# s02_power.net
KiCad netlist of a schematic drawn in Altium Designer
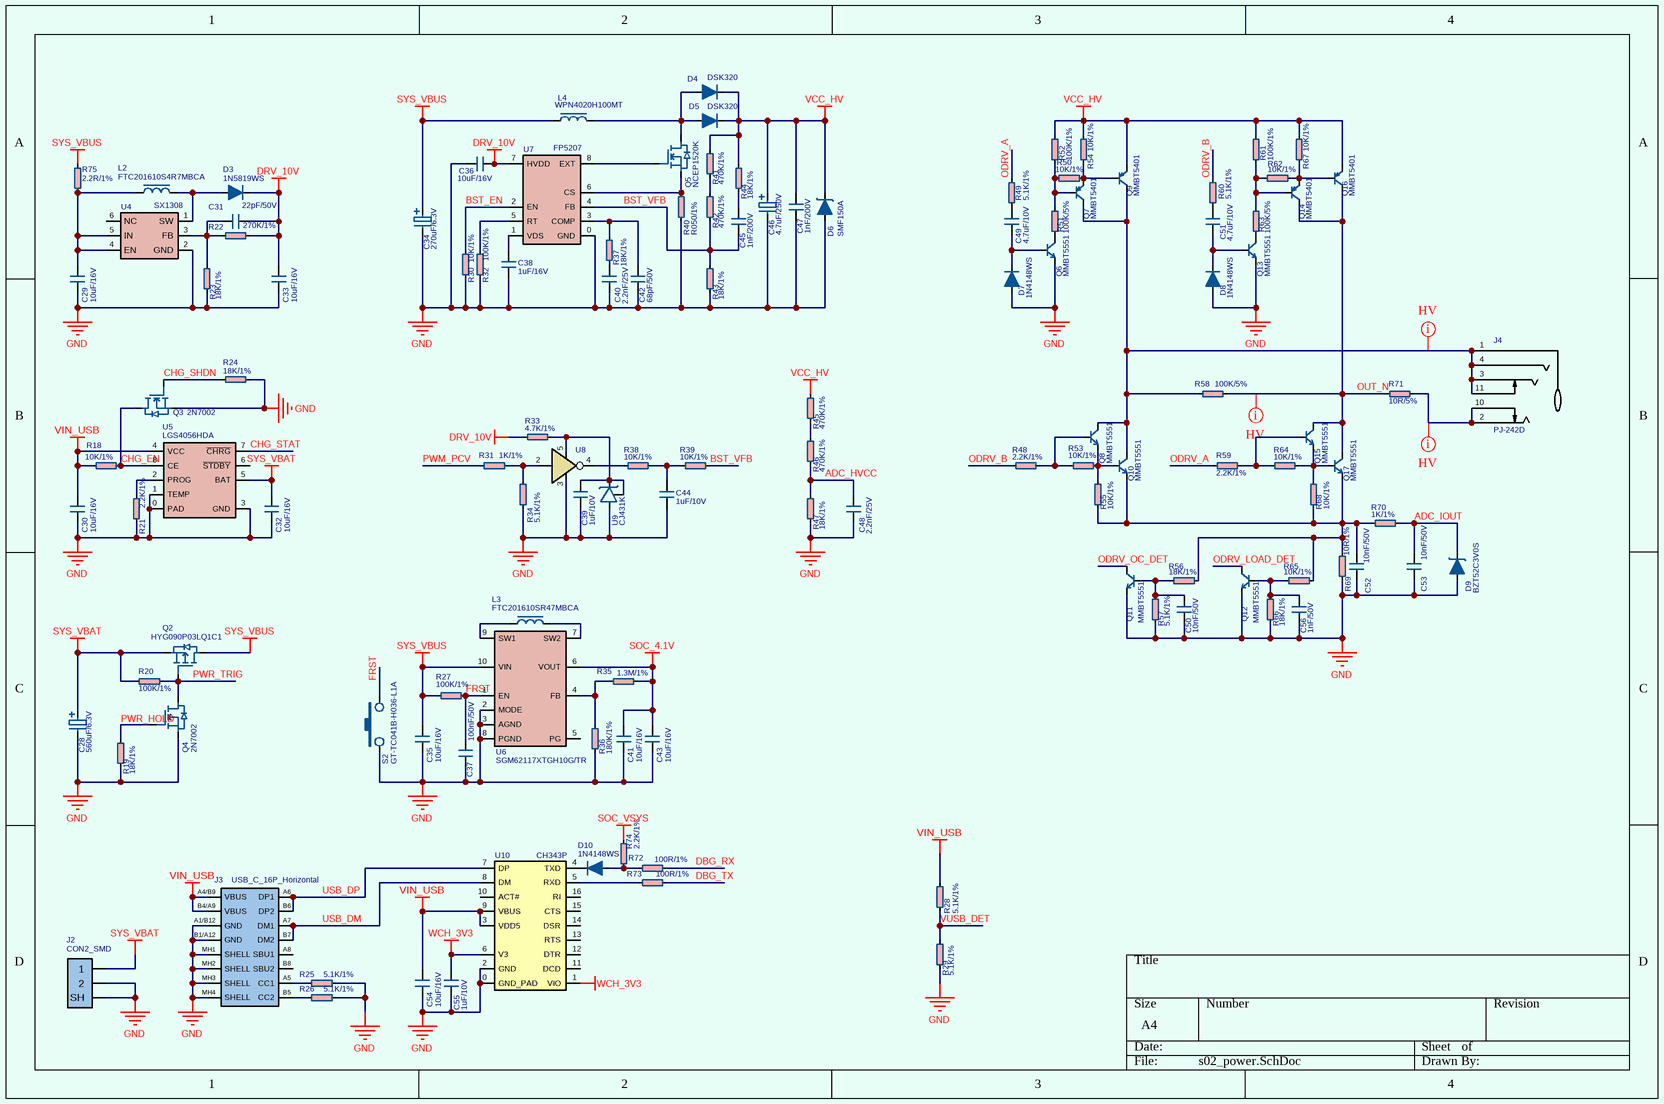
[diagram p0: s02_power.SchDoc]

(export (version "E")
  (design (tool "Eeschema 10.0.6"))
  (components
    (comp (ref "C28")
      (value "560uF/6.3V")
      (footprint "CAP_EL_DIP_6.3X11_HOR_REV")
      (libsource (lib "LibMySelf_SCHLIB") (part "CAP_EL"))
    )
    (comp (ref "C29")
      (value "10uF/16V")
      (footprint "0603C")
      (libsource (lib "LibMySelf_SCHLIB") (part "CAP"))
    )
    (comp (ref "C30")
      (value "10uF/16V")
      (footprint "0603C")
      (libsource (lib "LibMySelf_SCHLIB") (part "CAP"))
    )
    (comp (ref "C31")
      (value "22pF/50V")
      (footprint "0402C")
      (libsource (lib "LibMySelf_SCHLIB") (part "CAP"))
    )
    (comp (ref "C32")
      (value "10uF/16V")
      (footprint "0603C")
      (libsource (lib "LibMySelf_SCHLIB") (part "CAP"))
    )
    (comp (ref "C33")
      (value "10uF/16V")
      (footprint "0603C")
      (libsource (lib "LibMySelf_SCHLIB") (part "CAP"))
    )
    (comp (ref "C34")
      (value "270uF/6.3V")
      (footprint "CAP_EL_DIP_6.3X11_HOR_REV")
      (libsource (lib "LibMySelf_SCHLIB") (part "CAP_EL"))
    )
    (comp (ref "C35")
      (value "10uF/16V")
      (footprint "0603C")
      (libsource (lib "LibMySelf_SCHLIB") (part "CAP"))
    )
    (comp (ref "C36")
      (value "10uF/16V")
      (footprint "0603C")
      (libsource (lib "LibMySelf_SCHLIB") (part "CAP"))
    )
    (comp (ref "C37")
      (value "100nF/50V")
      (footprint "0402C")
      (libsource (lib "LibMySelf_SCHLIB") (part "CAP"))
    )
    (comp (ref "C38") (value "1uF/16V") (footprint "0402C") (libsource (lib "LibMySelf_SCHLIB") (part "CAP")))
    (comp (ref "C39") (value "1uF/10V") (footprint "0402C") (libsource (lib "LibMySelf_SCHLIB") (part "CAP")))
    (comp (ref "C40")
      (value "2.2nF/25V")
      (footprint "0402C")
      (libsource (lib "LibMySelf_SCHLIB") (part "CAP"))
    )
    (comp (ref "C41")
      (value "10uF/16V")
      (footprint "0603C")
      (libsource (lib "LibMySelf_SCHLIB") (part "CAP"))
    )
    (comp (ref "C42")
      (value "68pF/50V")
      (footprint "0402C")
      (libsource (lib "LibMySelf_SCHLIB") (part "CAP"))
    )
    (comp (ref "C43")
      (value "10uF/16V")
      (footprint "0603C")
      (libsource (lib "LibMySelf_SCHLIB") (part "CAP"))
    )
    (comp (ref "C44") (value "1uF/10V") (footprint "0402C") (libsource (lib "LibMySelf_SCHLIB") (part "CAP")))
    (comp (ref "C45")
      (value "1nF/200V")
      (footprint "0805C_N_HD")
      (description "CC0805JRNPOABN102")
      (libsource (lib "LibMySelf_SCHLIB") (part "CAP"))
    )
    (comp (ref "C46")
      (value "4.7uF/250V")
      (footprint "CAP_EL_DIP_6.3X11_HOR_REV")
      (libsource (lib "LibMySelf_SCHLIB") (part "CAP_EL"))
    )
    (comp (ref "C47")
      (value "1nF/200V")
      (footprint "0805C_N_HD")
      (description "CC0805JRNPOABN102")
      (libsource (lib "LibMySelf_SCHLIB") (part "CAP"))
    )
    (comp (ref "C48")
      (value "2.2nF/25V")
      (footprint "0402C")
      (libsource (lib "LibMySelf_SCHLIB") (part "CAP"))
    )
    (comp (ref "C49")
      (value "4.7uF/10V")
      (footprint "0402C")
      (libsource (lib "LibMySelf_SCHLIB") (part "CAP"))
    )
    (comp (ref "C50")
      (value "10nF/50V")
      (footprint "0402C")
      (libsource (lib "LibMySelf_SCHLIB") (part "CAP"))
    )
    (comp (ref "C51")
      (value "4.7uF/10V")
      (footprint "0402C")
      (libsource (lib "LibMySelf_SCHLIB") (part "CAP"))
    )
    (comp (ref "C52")
      (value "10nF/50V")
      (footprint "0402C")
      (libsource (lib "LibMySelf_SCHLIB") (part "CAP"))
    )
    (comp (ref "C53")
      (value "10nF/50V")
      (footprint "0402C")
      (libsource (lib "LibMySelf_SCHLIB") (part "CAP"))
    )
    (comp (ref "C54")
      (value "10uF/16V")
      (footprint "0603C")
      (libsource (lib "LibMySelf_SCHLIB") (part "CAP"))
    )
    (comp (ref "C55") (value "1uF/10V") (footprint "0402C") (libsource (lib "LibMySelf_SCHLIB") (part "CAP")))
    (comp (ref "C56") (value "1nF/50V") (footprint "0402C") (libsource (lib "LibMySelf_SCHLIB") (part "CAP")))
    (comp (ref "D3")
      (value "1N5819WS")
      (footprint "SOD323_N")
      (libsource (lib "LibMySelf_SCHLIB") (part "VD"))
    )
    (comp (ref "D4")
      (value "DSK320")
      (footprint "SOD123_N_HD")
      (libsource (lib "LibMySelf_SCHLIB") (part "VD"))
    )
    (comp (ref "D5")
      (value "DSK320")
      (footprint "SOD123_N_HD")
      (libsource (lib "LibMySelf_SCHLIB") (part "VD"))
    )
    (comp (ref "D6")
      (value "SMF150A")
      (footprint "SOD123_N_HD")
      (libsource (lib "LibMySelf_SCHLIB") (part "VS"))
    )
    (comp (ref "D7") (value "1N4148WS") (footprint "SOD323") (libsource (lib "LibMySelf_SCHLIB") (part "VD")))
    (comp (ref "D8") (value "1N4148WS") (footprint "SOD323") (libsource (lib "LibMySelf_SCHLIB") (part "VD")))
    (comp (ref "D9")
      (value "BZT52C3V0S")
      (footprint "SOD323_N")
      (libsource (lib "LibMySelf_SCHLIB") (part "VS"))
    )
    (comp (ref "D10")
      (value "1N4148WS")
      (footprint "SOD323")
      (libsource (lib "LibMySelf_SCHLIB") (part "VD"))
    )
    (comp (ref "J2")
      (value "CON2_SMD")
      (footprint "PRT_1.25MM_2PIN_HOR_SMD")
      (libsource (lib "LibMySelf_SCHLIB") (part "CON2_SMD"))
    )
    (comp (ref "J3")
      (value "USB_C_16P_Horizontal")
      (footprint "USB_C_16P_FEMALE_HOR_L7.3_HD")
      (libsource (lib "LibMySelf_SCHLIB") (part "USB_TYPEC_16P_Horizontal_4MP"))
    )
    (comp (ref "J4")
      (value "PJ-242D")
      (footprint "CON_AUDIO_PJ_242")
      (libsource (lib "LibMySelf_SCHLIB") (part "CON_AUDIO_PJ_242D"))
    )
    (comp (ref "L2")
      (value "FTC201610S4R7MBCA")
      (footprint "INDUCTOR_0806_HD")
      (libsource (lib "LibMySelf_SCHLIB") (part "INDUCTOR"))
    )
    (comp (ref "L3")
      (value "FTC201610SR47MBCA")
      (footprint "INDUCTOR_0806_HD")
      (libsource (lib "LibMySelf_SCHLIB") (part "INDUCTOR"))
    )
    (comp (ref "L4")
      (value "WPN4020H100MT")
      (footprint "INDUCTOR_SWPA4020S")
      (libsource (lib "LibMySelf_SCHLIB") (part "INDUCTOR"))
    )
    (comp (ref "Q2")
      (value "HYG090P03LQ1C1")
      (footprint "DFN8_MOS_3X3")
      (libsource (lib "LibMySelf_SCHLIB") (part "MOS_P"))
    )
    (comp (ref "Q3")
      (value "2N7002")
      (footprint "SOT23_MOS")
      (libsource (lib "LibMySelf_SCHLIB") (part "MOS_N"))
    )
    (comp (ref "Q4")
      (value "2N7002")
      (footprint "SOT23_MOS")
      (libsource (lib "LibMySelf_SCHLIB") (part "MOS_N"))
    )
    (comp (ref "Q5")
      (value "NCEP1520K")
      (footprint "TO252_MOS")
      (libsource (lib "LibMySelf_SCHLIB") (part "MOS_N"))
    )
    (comp (ref "Q6")
      (value "MMBT5551")
      (footprint "SOT23_BCE")
      (libsource (lib "LibMySelf_SCHLIB") (part "BJT_NPN"))
    )
    (comp (ref "Q7")
      (value "MMBT5401")
      (footprint "SOT23_BCE")
      (libsource (lib "LibMySelf_SCHLIB") (part "BJT_PNP"))
    )
    (comp (ref "Q8")
      (value "MMBT5551")
      (footprint "SOT23_BCE")
      (libsource (lib "LibMySelf_SCHLIB") (part "BJT_NPN"))
    )
    (comp (ref "Q9")
      (value "MMBT5401")
      (footprint "SOT23_BCE")
      (libsource (lib "LibMySelf_SCHLIB") (part "BJT_PNP"))
    )
    (comp (ref "Q10")
      (value "MMBT5551")
      (footprint "SOT23_BCE")
      (libsource (lib "LibMySelf_SCHLIB") (part "BJT_NPN"))
    )
    (comp (ref "Q11")
      (value "MMBT5551")
      (footprint "SOT23_BCE")
      (libsource (lib "LibMySelf_SCHLIB") (part "BJT_NPN"))
    )
    (comp (ref "Q12")
      (value "MMBT5551")
      (footprint "SOT23_BCE")
      (libsource (lib "LibMySelf_SCHLIB") (part "BJT_NPN"))
    )
    (comp (ref "Q13")
      (value "MMBT5551")
      (footprint "SOT23_BCE")
      (libsource (lib "LibMySelf_SCHLIB") (part "BJT_NPN"))
    )
    (comp (ref "Q14")
      (value "MMBT5401")
      (footprint "SOT23_BCE")
      (libsource (lib "LibMySelf_SCHLIB") (part "BJT_PNP"))
    )
    (comp (ref "Q15")
      (value "MMBT5551")
      (footprint "SOT23_BCE")
      (libsource (lib "LibMySelf_SCHLIB") (part "BJT_NPN"))
    )
    (comp (ref "Q16")
      (value "MMBT5401")
      (footprint "SOT23_BCE")
      (libsource (lib "LibMySelf_SCHLIB") (part "BJT_PNP"))
    )
    (comp (ref "Q17")
      (value "MMBT5551")
      (footprint "SOT23_BCE")
      (libsource (lib "LibMySelf_SCHLIB") (part "BJT_NPN"))
    )
    (comp (ref "R18") (value "10K/1%") (footprint "0402R") (libsource (lib "LibMySelf_SCHLIB") (part "RES")))
    (comp (ref "R19") (value "18K/1%") (footprint "0402R") (libsource (lib "LibMySelf_SCHLIB") (part "RES")))
    (comp (ref "R20") (value "100K/1%") (footprint "0402R") (libsource (lib "LibMySelf_SCHLIB") (part "RES")))
    (comp (ref "R21") (value "2.2K/1%") (footprint "0402R") (libsource (lib "LibMySelf_SCHLIB") (part "RES")))
    (comp (ref "R22") (value "270K/1%") (footprint "0402R") (libsource (lib "LibMySelf_SCHLIB") (part "RES")))
    (comp (ref "R23") (value "18K/1%") (footprint "0402R") (libsource (lib "LibMySelf_SCHLIB") (part "RES")))
    (comp (ref "R24") (value "18K/1%") (footprint "0402R") (libsource (lib "LibMySelf_SCHLIB") (part "RES")))
    (comp (ref "R25") (value "5.1K/1%") (footprint "0402R") (libsource (lib "LibMySelf_SCHLIB") (part "RES")))
    (comp (ref "R26") (value "5.1K/1%") (footprint "0402R") (libsource (lib "LibMySelf_SCHLIB") (part "RES")))
    (comp (ref "R27") (value "100K/1%") (footprint "0402R") (libsource (lib "LibMySelf_SCHLIB") (part "RES")))
    (comp (ref "R28") (value "5.1K/1%") (footprint "0402R") (libsource (lib "LibMySelf_SCHLIB") (part "RES")))
    (comp (ref "R29") (value "5.1K/1%") (footprint "0402R") (libsource (lib "LibMySelf_SCHLIB") (part "RES")))
    (comp (ref "R30") (value "10K/1%") (footprint "0402R") (libsource (lib "LibMySelf_SCHLIB") (part "RES")))
    (comp (ref "R31") (value "1K/1%") (footprint "0402R") (libsource (lib "LibMySelf_SCHLIB") (part "RES")))
    (comp (ref "R32") (value "100K/1%") (footprint "0402R") (libsource (lib "LibMySelf_SCHLIB") (part "RES")))
    (comp (ref "R33") (value "4.7K/1%") (footprint "0402R") (libsource (lib "LibMySelf_SCHLIB") (part "RES")))
    (comp (ref "R34") (value "5.1K/1%") (footprint "0402R") (libsource (lib "LibMySelf_SCHLIB") (part "RES")))
    (comp (ref "R35") (value "1.3M/1%") (footprint "0402R") (libsource (lib "LibMySelf_SCHLIB") (part "RES")))
    (comp (ref "R36") (value "180K/1%") (footprint "0402R") (libsource (lib "LibMySelf_SCHLIB") (part "RES")))
    (comp (ref "R37") (value "18K/1%") (footprint "0402R") (libsource (lib "LibMySelf_SCHLIB") (part "RES")))
    (comp (ref "R38") (value "10K/1%") (footprint "0402R") (libsource (lib "LibMySelf_SCHLIB") (part "RES")))
    (comp (ref "R39") (value "10K/1%") (footprint "0402R") (libsource (lib "LibMySelf_SCHLIB") (part "RES")))
    (comp (ref "R40")
      (value "R050/1%")
      (footprint "1206R_N_HD")
      (libsource (lib "LibMySelf_SCHLIB") (part "RES"))
    )
    (comp (ref "R41")
      (value "470K/1%")
      (footprint "0805R_N_HD")
      (libsource (lib "LibMySelf_SCHLIB") (part "RES"))
    )
    (comp (ref "R42")
      (value "470K/1%")
      (footprint "0805R_N_HD")
      (libsource (lib "LibMySelf_SCHLIB") (part "RES"))
    )
    (comp (ref "R43") (value "18K/1%") (footprint "0402R") (libsource (lib "LibMySelf_SCHLIB") (part "RES")))
    (comp (ref "R44") (value "18K/1%") (footprint "0402R") (libsource (lib "LibMySelf_SCHLIB") (part "RES")))
    (comp (ref "R45")
      (value "470K/1%")
      (footprint "0805R_N_HD")
      (libsource (lib "LibMySelf_SCHLIB") (part "RES"))
    )
    (comp (ref "R46")
      (value "470K/1%")
      (footprint "0805R_N_HD")
      (libsource (lib "LibMySelf_SCHLIB") (part "RES"))
    )
    (comp (ref "R47") (value "18K/1%") (footprint "0402R") (libsource (lib "LibMySelf_SCHLIB") (part "RES")))
    (comp (ref "R48") (value "2.2K/1%") (footprint "0402R") (libsource (lib "LibMySelf_SCHLIB") (part "RES")))
    (comp (ref "R49") (value "5.1K/1%") (footprint "0402R") (libsource (lib "LibMySelf_SCHLIB") (part "RES")))
    (comp (ref "R50") (value "10K/1%") (footprint "0402R") (libsource (lib "LibMySelf_SCHLIB") (part "RES")))
    (comp (ref "R51") (value "100K/5%") (footprint "0805R") (libsource (lib "LibMySelf_SCHLIB") (part "RES")))
    (comp (ref "R52") (value "100K/1%") (footprint "0402R") (libsource (lib "LibMySelf_SCHLIB") (part "RES")))
    (comp (ref "R53") (value "10K/1%") (footprint "0402R") (libsource (lib "LibMySelf_SCHLIB") (part "RES")))
    (comp (ref "R54") (value "10K/1%") (footprint "0402R") (libsource (lib "LibMySelf_SCHLIB") (part "RES")))
    (comp (ref "R55") (value "10K/1%") (footprint "0402R") (libsource (lib "LibMySelf_SCHLIB") (part "RES")))
    (comp (ref "R56") (value "18K/1%") (footprint "0402R") (libsource (lib "LibMySelf_SCHLIB") (part "RES")))
    (comp (ref "R57") (value "5.1K/1%") (footprint "0402R") (libsource (lib "LibMySelf_SCHLIB") (part "RES")))
    (comp (ref "R58") (value "100K/5%") (footprint "0805R") (libsource (lib "LibMySelf_SCHLIB") (part "RES")))
    (comp (ref "R59") (value "2.2K/1%") (footprint "0402R") (libsource (lib "LibMySelf_SCHLIB") (part "RES")))
    (comp (ref "R60") (value "5.1K/1%") (footprint "0402R") (libsource (lib "LibMySelf_SCHLIB") (part "RES")))
    (comp (ref "R61") (value "100K/1%") (footprint "0402R") (libsource (lib "LibMySelf_SCHLIB") (part "RES")))
    (comp (ref "R62") (value "10K/1%") (footprint "0402R") (libsource (lib "LibMySelf_SCHLIB") (part "RES")))
    (comp (ref "R63") (value "100K/5%") (footprint "0805R") (libsource (lib "LibMySelf_SCHLIB") (part "RES")))
    (comp (ref "R64") (value "10K/1%") (footprint "0402R") (libsource (lib "LibMySelf_SCHLIB") (part "RES")))
    (comp (ref "R65") (value "10K/1%") (footprint "0402R") (libsource (lib "LibMySelf_SCHLIB") (part "RES")))
    (comp (ref "R66") (value "18K/1%") (footprint "0402R") (libsource (lib "LibMySelf_SCHLIB") (part "RES")))
    (comp (ref "R67") (value "10K/1%") (footprint "0402R") (libsource (lib "LibMySelf_SCHLIB") (part "RES")))
    (comp (ref "R68") (value "10K/1%") (footprint "0402R") (libsource (lib "LibMySelf_SCHLIB") (part "RES")))
    (comp (ref "R69")
      (value "10R/1%")
      (footprint "0805R_N_HD")
      (libsource (lib "LibMySelf_SCHLIB") (part "RES"))
    )
    (comp (ref "R70") (value "1K/1%") (footprint "0402R") (libsource (lib "LibMySelf_SCHLIB") (part "RES")))
    (comp (ref "R71") (value "10R/5%") (footprint "0805R") (libsource (lib "LibMySelf_SCHLIB") (part "RES")))
    (comp (ref "R72") (value "100R/1%") (footprint "0402R") (libsource (lib "LibMySelf_SCHLIB") (part "RES")))
    (comp (ref "R73") (value "100R/1%") (footprint "0402R") (libsource (lib "LibMySelf_SCHLIB") (part "RES")))
    (comp (ref "R74") (value "2.2K/1%") (footprint "0402R") (libsource (lib "LibMySelf_SCHLIB") (part "RES")))
    (comp (ref "R75") (value "2.2R/1%") (footprint "0402R") (libsource (lib "LibMySelf_SCHLIB") (part "RES")))
    (comp (ref "S2")
      (value "GT-TC041B-H036-L1A")
      (footprint "SW_MEDIUM_TURTLE")
      (libsource (lib "LibMySelf_SCHLIB") (part "SW_PB"))
    )
    (comp (ref "U4")
      (value "SX1308")
      (footprint "SOT23_6")
      (libsource (lib "LibMySelf_SCHLIB") (part "SX1308"))
    )
    (comp (ref "U5")
      (value "LGS4056HDA")
      (footprint "DFN8_0.5_2X2")
      (libsource (lib "LibMySelf_SCHLIB") (part "TP4056"))
    )
    (comp (ref "U6")
      (value "SGM62117XTGH10G/TR")
      (footprint "DFN8_0.5_3X2_SGM62117")
      (description "Buck-Boost Converter, 18uA, 2.2 to 5.5V IN, 1.8 to 5.2V OUT")
      (libsource (lib "LibMySelf_SCHLIB") (part "SGM62117"))
    )
    (comp (ref "U7")
      (value "FP5207")
      (footprint "SOP8_150MIL_PAD_N_HD")
      (libsource (lib "LibMySelf_SCHLIB") (part "FP5207"))
    )
    (comp (ref "U8")
      (value "SN74LVC1G14DBVR")
      (footprint "SOT23_5")
      (description "1-Channel Schmitt-Trigger Inverter Gate")
      (libsource (lib "LibMySelf_SCHLIB") (part "SN74AHC1G14"))
    )
    (comp (ref "U9") (value "CJ431K") (footprint "SOT23") (libsource (lib "LibMySelf_SCHLIB") (part "TL431")))
    (comp (ref "U10")
      (value "CH343P")
      (footprint "QFN16_0.5_3X3")
      (description "USB to UART converter")
      (libsource (lib "LibMySelf_SCHLIB") (part "CH343P"))
    )
  )
  (nets
    (net (code "1") (name "/ADC_HVCC") (class "Default")
      (node (ref "C48") (pin "2") (pinfunction "2_2") (pintype "passive"))
      (node (ref "R46") (pin "1") (pinfunction "1_1") (pintype "passive"))
      (node (ref "R47") (pin "2") (pinfunction "2_2") (pintype "passive"))
    )
    (net (code "2") (name "/ADC_IOUT") (class "Default")
      (node (ref "C53") (pin "2") (pinfunction "2_2") (pintype "passive"))
      (node (ref "D9") (pin "2") (pinfunction "2_2") (pintype "passive"))
      (node (ref "R70") (pin "1") (pinfunction "1_1") (pintype "passive"))
    )
    (net (code "3") (name "/BST_EN") (class "Default")
      (node (ref "R30") (pin "2") (pinfunction "2_2") (pintype "passive"))
      (node (ref "U7") (pin "2") (pinfunction "EN_2") (pintype "passive"))
    )
    (net (code "4") (name "/BST_VFB") (class "Default")
      (node (ref "C45") (pin "1") (pinfunction "1_1") (pintype "passive"))
      (node (ref "R39") (pin "1") (pinfunction "1_1") (pintype "passive"))
      (node (ref "R42") (pin "1") (pinfunction "1_1") (pintype "passive"))
      (node (ref "R43") (pin "2") (pinfunction "2_2") (pintype "passive"))
      (node (ref "U7") (pin "4") (pinfunction "FB_4") (pintype "passive"))
    )
    (net (code "5") (name "/CHG_EN") (class "Default")
      (node (ref "Q3") (pin "D") (pinfunction "D_D") (pintype "passive"))
      (node (ref "R18") (pin "1") (pinfunction "1_1") (pintype "passive"))
      (node (ref "U5") (pin "8") (pinfunction "CE_8") (pintype "passive"))
    )
    (net (code "6") (name "/CHG_SHDN") (class "Default")
      (node (ref "Q3") (pin "G") (pinfunction "G_G") (pintype "passive"))
      (node (ref "R24") (pin "2") (pinfunction "2_2") (pintype "passive"))
    )
    (net (code "7") (name "/CHG_STAT") (class "Default")
      (node (ref "U5") (pin "7") (pinfunction "~{CHRG}_7") (pintype "passive"))
    )
    (net (code "8") (name "/DBG_RX") (class "Default")
      (node (ref "R72") (pin "1") (pinfunction "1_1") (pintype "passive"))
    )
    (net (code "9") (name "/DBG_TX") (class "Default")
      (node (ref "R73") (pin "1") (pinfunction "1_1") (pintype "passive"))
    )
    (net (code "10") (name "/FRST") (class "Default")
      (node (ref "C37") (pin "2") (pinfunction "2_2") (pintype "passive"))
      (node (ref "R27") (pin "1") (pinfunction "1_1") (pintype "passive"))
      (node (ref "S2") (pin "1") (pinfunction "1_1") (pintype "passive"))
      (node (ref "U6") (pin "1") (pinfunction "EN_1") (pintype "passive"))
    )
    (net (code "11") (name "/ODRV_A") (class "Default")
      (node (ref "R49") (pin "2") (pinfunction "2_2") (pintype "passive"))
      (node (ref "R59") (pin "2") (pinfunction "2_2") (pintype "passive"))
    )
    (net (code "12") (name "/ODRV_B") (class "Default")
      (node (ref "R48") (pin "2") (pinfunction "2_2") (pintype "passive"))
      (node (ref "R60") (pin "2") (pinfunction "2_2") (pintype "passive"))
    )
    (net (code "13") (name "/ODRV_LOAD_DET") (class "Default")
      (node (ref "Q12") (pin "C") (pinfunction "C_C") (pintype "passive"))
    )
    (net (code "14") (name "/ODRV_OC_DET") (class "Default")
      (node (ref "Q11") (pin "C") (pinfunction "C_C") (pintype "passive"))
    )
    (net (code "15") (name "/OUT_N") (class "Default")
      (node (ref "Q14") (pin "C") (pinfunction "C_C") (pintype "passive"))
      (node (ref "Q15") (pin "C") (pinfunction "C_C") (pintype "passive"))
      (node (ref "Q16") (pin "C") (pinfunction "C_C") (pintype "passive"))
      (node (ref "Q17") (pin "C") (pinfunction "C_C") (pintype "passive"))
      (node (ref "R58") (pin "2") (pinfunction "2_2") (pintype "passive"))
      (node (ref "R71") (pin "2") (pinfunction "2_2") (pintype "passive"))
    )
    (net (code "16") (name "/PWM_PCV") (class "Default")
      (node (ref "R31") (pin "2") (pinfunction "2_2") (pintype "passive"))
    )
    (net (code "17") (name "/PWR_HOLD") (class "Default")
      (node (ref "Q4") (pin "G") (pinfunction "G_G") (pintype "passive"))
      (node (ref "R19") (pin "2") (pinfunction "2_2") (pintype "passive"))
    )
    (net (code "18") (name "/PWR_TRIG") (class "Default")
      (node (ref "Q2") (pin "G") (pinfunction "G_G") (pintype "passive"))
      (node (ref "Q4") (pin "D") (pinfunction "D_D") (pintype "passive"))
      (node (ref "R20") (pin "1") (pinfunction "1_1") (pintype "passive"))
    )
    (net (code "19") (name "/USB_DM") (class "Default")
      (node (ref "J3") (pin "A7") (pinfunction "DM1_A7") (pintype "passive"))
      (node (ref "J3") (pin "B7") (pinfunction "DM2_B7") (pintype "passive"))
      (node (ref "U10") (pin "8") (pinfunction "DM_8") (pintype "passive"))
    )
    (net (code "20") (name "/USB_DP") (class "Default")
      (node (ref "J3") (pin "A6") (pinfunction "DP1_A6") (pintype "passive"))
      (node (ref "J3") (pin "B6") (pinfunction "DP2_B6") (pintype "passive"))
      (node (ref "U10") (pin "7") (pinfunction "DP_7") (pintype "passive"))
    )
    (net (code "21") (name "/VUSB_DET") (class "Default")
      (node (ref "R28") (pin "1") (pinfunction "1_1") (pintype "passive"))
      (node (ref "R29") (pin "2") (pinfunction "2_2") (pintype "passive"))
    )
    (net (code "22") (name "DRV_10V") (class "Default")
      (node (ref "C31") (pin "1") (pinfunction "1_1") (pintype "passive"))
      (node (ref "C33") (pin "1") (pinfunction "1_1") (pintype "passive"))
      (node (ref "C36") (pin "1") (pinfunction "1_1") (pintype "passive"))
      (node (ref "D3") (pin "2") (pinfunction "2_2") (pintype "passive"))
      (node (ref "R22") (pin "1") (pinfunction "1_1") (pintype "passive"))
      (node (ref "R33") (pin "1") (pinfunction "1_1") (pintype "passive"))
      (node (ref "U7") (pin "7") (pinfunction "HVDD_7") (pintype "passive"))
    )
    (net (code "23") (name "GND") (class "Default")
      (node (ref "C28") (pin "2") (pinfunction "2_2") (pintype "passive"))
      (node (ref "C29") (pin "2") (pinfunction "2_2") (pintype "passive"))
      (node (ref "C30") (pin "2") (pinfunction "2_2") (pintype "passive"))
      (node (ref "C32") (pin "2") (pinfunction "2_2") (pintype "passive"))
      (node (ref "C33") (pin "2") (pinfunction "2_2") (pintype "passive"))
      (node (ref "C34") (pin "2") (pinfunction "2_2") (pintype "passive"))
      (node (ref "C35") (pin "2") (pinfunction "2_2") (pintype "passive"))
      (node (ref "C36") (pin "2") (pinfunction "2_2") (pintype "passive"))
      (node (ref "C37") (pin "1") (pinfunction "1_1") (pintype "passive"))
      (node (ref "C38") (pin "1") (pinfunction "1_1") (pintype "passive"))
      (node (ref "C39") (pin "1") (pinfunction "1_1") (pintype "passive"))
      (node (ref "C40") (pin "1") (pinfunction "1_1") (pintype "passive"))
      (node (ref "C41") (pin "2") (pinfunction "2_2") (pintype "passive"))
      (node (ref "C42") (pin "1") (pinfunction "1_1") (pintype "passive"))
      (node (ref "C43") (pin "2") (pinfunction "2_2") (pintype "passive"))
      (node (ref "C44") (pin "1") (pinfunction "1_1") (pintype "passive"))
      (node (ref "C46") (pin "2") (pinfunction "2_2") (pintype "passive"))
      (node (ref "C47") (pin "1") (pinfunction "1_1") (pintype "passive"))
      (node (ref "C48") (pin "1") (pinfunction "1_1") (pintype "passive"))
      (node (ref "C50") (pin "1") (pinfunction "1_1") (pintype "passive"))
      (node (ref "C52") (pin "1") (pinfunction "1_1") (pintype "passive"))
      (node (ref "C53") (pin "1") (pinfunction "1_1") (pintype "passive"))
      (node (ref "C54") (pin "2") (pinfunction "2_2") (pintype "passive"))
      (node (ref "C55") (pin "1") (pinfunction "1_1") (pintype "passive"))
      (node (ref "C56") (pin "1") (pinfunction "1_1") (pintype "passive"))
      (node (ref "D6") (pin "1") (pinfunction "1_1") (pintype "passive"))
      (node (ref "D7") (pin "1") (pinfunction "1_1") (pintype "passive"))
      (node (ref "D8") (pin "1") (pinfunction "1_1") (pintype "passive"))
      (node (ref "D9") (pin "1") (pinfunction "1_1") (pintype "passive"))
      (node (ref "J2") (pin "0") (pinfunction "SH_0") (pintype "passive"))
      (node (ref "J2") (pin "2") (pinfunction "2_2") (pintype "passive"))
      (node (ref "J3") (pin "A1/B12") (pinfunction "GND_A1/B12") (pintype "passive"))
      (node (ref "J3") (pin "B1/A12") (pinfunction "GND_B1/A12") (pintype "passive"))
      (node (ref "J3") (pin "MH1") (pinfunction "SHELL_MH1") (pintype "passive"))
      (node (ref "J3") (pin "MH2") (pinfunction "SHELL_MH2") (pintype "passive"))
      (node (ref "J3") (pin "MH3") (pinfunction "SHELL_MH3") (pintype "passive"))
      (node (ref "J3") (pin "MH4") (pinfunction "SHELL_MH4") (pintype "passive"))
      (node (ref "Q11") (pin "E") (pinfunction "E_E") (pintype "passive"))
      (node (ref "Q12") (pin "E") (pinfunction "E_E") (pintype "passive"))
      (node (ref "Q13") (pin "E") (pinfunction "E_E") (pintype "passive"))
      (node (ref "Q3") (pin "S") (pinfunction "S_S") (pintype "passive"))
      (node (ref "Q4") (pin "S") (pinfunction "S_S") (pintype "passive"))
      (node (ref "Q6") (pin "E") (pinfunction "E_E") (pintype "passive"))
      (node (ref "R19") (pin "1") (pinfunction "1_1") (pintype "passive"))
      (node (ref "R21") (pin "2") (pinfunction "2_2") (pintype "passive"))
      (node (ref "R23") (pin "1") (pinfunction "1_1") (pintype "passive"))
      (node (ref "R24") (pin "1") (pinfunction "1_1") (pintype "passive"))
      (node (ref "R25") (pin "1") (pinfunction "1_1") (pintype "passive"))
      (node (ref "R26") (pin "1") (pinfunction "1_1") (pintype "passive"))
      (node (ref "R29") (pin "1") (pinfunction "1_1") (pintype "passive"))
      (node (ref "R30") (pin "1") (pinfunction "1_1") (pintype "passive"))
      (node (ref "R32") (pin "1") (pinfunction "1_1") (pintype "passive"))
      (node (ref "R34") (pin "2") (pinfunction "2_2") (pintype "passive"))
      (node (ref "R36") (pin "2") (pinfunction "2_2") (pintype "passive"))
      (node (ref "R40") (pin "1") (pinfunction "1_1") (pintype "passive"))
      (node (ref "R43") (pin "1") (pinfunction "1_1") (pintype "passive"))
      (node (ref "R47") (pin "1") (pinfunction "1_1") (pintype "passive"))
      (node (ref "R57") (pin "2") (pinfunction "2_2") (pintype "passive"))
      (node (ref "R66") (pin "2") (pinfunction "2_2") (pintype "passive"))
      (node (ref "R69") (pin "2") (pinfunction "2_2") (pintype "passive"))
      (node (ref "S2") (pin "2") (pinfunction "2_2") (pintype "passive"))
      (node (ref "U10") (pin "0") (pinfunction "GND_PAD_0") (pintype "passive"))
      (node (ref "U10") (pin "2") (pinfunction "GND_2") (pintype "passive"))
      (node (ref "U4") (pin "2") (pinfunction "GND_2") (pintype "passive"))
      (node (ref "U5") (pin "0") (pinfunction "PAD_0") (pintype "passive"))
      (node (ref "U5") (pin "1") (pinfunction "TEMP_1") (pintype "passive"))
      (node (ref "U5") (pin "3") (pinfunction "GND_3") (pintype "passive"))
      (node (ref "U6") (pin "2") (pinfunction "MODE_2") (pintype "passive"))
      (node (ref "U6") (pin "3") (pinfunction "AGND_3") (pintype "passive"))
      (node (ref "U6") (pin "8") (pinfunction "PGND_8") (pintype "passive"))
      (node (ref "U7") (pin "0") (pinfunction "GND_0") (pintype "passive"))
      (node (ref "U8") (pin "3") (pinfunction "G_3") (pintype "passive"))
      (node (ref "U9") (pin "3") (pinfunction "3_3") (pintype "passive"))
    )
    (net (code "24") (name "Net-(C40-Pad2)") (class "Default")
      (node (ref "C40") (pin "2") (pinfunction "2_2") (pintype "passive"))
      (node (ref "R37") (pin "1") (pinfunction "1_1") (pintype "passive"))
    )
    (net (code "25") (name "Net-(C44-Pad2)") (class "Default")
      (node (ref "C44") (pin "2") (pinfunction "2_2") (pintype "passive"))
      (node (ref "R38") (pin "1") (pinfunction "1_1") (pintype "passive"))
      (node (ref "R39") (pin "2") (pinfunction "2_2") (pintype "passive"))
    )
    (net (code "26") (name "Net-(C45-Pad2)") (class "Default")
      (node (ref "C45") (pin "2") (pinfunction "2_2") (pintype "passive"))
      (node (ref "R44") (pin "1") (pinfunction "1_1") (pintype "passive"))
    )
    (net (code "27") (name "Net-(C49-Pad1)") (class "Default")
      (node (ref "C49") (pin "1") (pinfunction "1_1") (pintype "passive"))
      (node (ref "R49") (pin "1") (pinfunction "1_1") (pintype "passive"))
    )
    (net (code "28") (name "Net-(C49-Pad2)") (class "Default")
      (node (ref "C49") (pin "2") (pinfunction "2_2") (pintype "passive"))
      (node (ref "D7") (pin "2") (pinfunction "2_2") (pintype "passive"))
      (node (ref "Q6") (pin "B") (pinfunction "B_B") (pintype "passive"))
    )
    (net (code "29") (name "Net-(C50-Pad2)") (class "Default")
      (node (ref "C50") (pin "2") (pinfunction "2_2") (pintype "passive"))
      (node (ref "Q11") (pin "B") (pinfunction "B_B") (pintype "passive"))
      (node (ref "R56") (pin "2") (pinfunction "2_2") (pintype "passive"))
      (node (ref "R57") (pin "1") (pinfunction "1_1") (pintype "passive"))
    )
    (net (code "30") (name "Net-(C51-Pad1)") (class "Default")
      (node (ref "C51") (pin "1") (pinfunction "1_1") (pintype "passive"))
      (node (ref "D8") (pin "2") (pinfunction "2_2") (pintype "passive"))
      (node (ref "Q13") (pin "B") (pinfunction "B_B") (pintype "passive"))
    )
    (net (code "31") (name "Net-(C51-Pad2)") (class "Default")
      (node (ref "C51") (pin "2") (pinfunction "2_2") (pintype "passive"))
      (node (ref "R60") (pin "1") (pinfunction "1_1") (pintype "passive"))
    )
    (net (code "32") (name "Net-(C52-Pad2)") (class "Default")
      (node (ref "C52") (pin "2") (pinfunction "2_2") (pintype "passive"))
      (node (ref "Q10") (pin "E") (pinfunction "E_E") (pintype "passive"))
      (node (ref "Q17") (pin "E") (pinfunction "E_E") (pintype "passive"))
      (node (ref "R55") (pin "1") (pinfunction "1_1") (pintype "passive"))
      (node (ref "R56") (pin "1") (pinfunction "1_1") (pintype "passive"))
      (node (ref "R65") (pin "1") (pinfunction "1_1") (pintype "passive"))
      (node (ref "R68") (pin "1") (pinfunction "1_1") (pintype "passive"))
      (node (ref "R69") (pin "1") (pinfunction "1_1") (pintype "passive"))
      (node (ref "R70") (pin "2") (pinfunction "2_2") (pintype "passive"))
    )
    (net (code "33") (name "Net-(C56-Pad2)") (class "Default")
      (node (ref "C56") (pin "2") (pinfunction "2_2") (pintype "passive"))
      (node (ref "Q12") (pin "B") (pinfunction "B_B") (pintype "passive"))
      (node (ref "R65") (pin "2") (pinfunction "2_2") (pintype "passive"))
      (node (ref "R66") (pin "1") (pinfunction "1_1") (pintype "passive"))
    )
    (net (code "34") (name "Net-(D4-Pad1)") (class "Default")
      (node (ref "D4") (pin "1") (pinfunction "1_1") (pintype "passive"))
      (node (ref "D5") (pin "1") (pinfunction "1_1") (pintype "passive"))
      (node (ref "L4") (pin "2") (pinfunction "2_2") (pintype "passive"))
      (node (ref "Q5") (pin "D") (pinfunction "D_D") (pintype "passive"))
    )
    (net (code "35") (name "Net-(D10-Pad1)") (class "Default")
      (node (ref "D10") (pin "1") (pinfunction "1_1") (pintype "passive"))
      (node (ref "R72") (pin "2") (pinfunction "2_2") (pintype "passive"))
      (node (ref "R74") (pin "2") (pinfunction "2_2") (pintype "passive"))
    )
    (net (code "36") (name "Net-(J3-CC1)") (class "Default")
      (node (ref "J3") (pin "A5") (pinfunction "CC1_A5") (pintype "passive"))
      (node (ref "R25") (pin "2") (pinfunction "2_2") (pintype "passive"))
    )
    (net (code "37") (name "Net-(J3-CC2)") (class "Default")
      (node (ref "J3") (pin "B5") (pinfunction "CC2_B5") (pintype "passive"))
      (node (ref "R26") (pin "2") (pinfunction "2_2") (pintype "passive"))
    )
    (net (code "38") (name "Net-(J4-Pad1)") (class "Default")
      (node (ref "J4") (pin "1") (pinfunction "1_1") (pintype "passive"))
      (node (ref "J4") (pin "11") (pinfunction "11_11") (pintype "passive"))
      (node (ref "J4") (pin "3") (pinfunction "3_3") (pintype "passive"))
      (node (ref "J4") (pin "4") (pinfunction "4_4") (pintype "passive"))
      (node (ref "Q10") (pin "C") (pinfunction "C_C") (pintype "passive"))
      (node (ref "Q7") (pin "C") (pinfunction "C_C") (pintype "passive"))
      (node (ref "Q8") (pin "C") (pinfunction "C_C") (pintype "passive"))
      (node (ref "Q9") (pin "C") (pinfunction "C_C") (pintype "passive"))
      (node (ref "R58") (pin "1") (pinfunction "1_1") (pintype "passive"))
    )
    (net (code "39") (name "Net-(J4-Pad10)") (class "Default")
      (node (ref "J4") (pin "10") (pinfunction "10_10") (pintype "passive"))
      (node (ref "J4") (pin "2") (pinfunction "2_2") (pintype "passive"))
      (node (ref "R71") (pin "1") (pinfunction "1_1") (pintype "passive"))
    )
    (net (code "40") (name "Net-(Q6-PadC)") (class "Default")
      (node (ref "Q6") (pin "C") (pinfunction "C_C") (pintype "passive"))
      (node (ref "R51") (pin "2") (pinfunction "2_2") (pintype "passive"))
    )
    (net (code "41") (name "Net-(Q7-PadB)") (class "Default")
      (node (ref "Q7") (pin "B") (pinfunction "B_B") (pintype "passive"))
      (node (ref "R50") (pin "2") (pinfunction "2_2") (pintype "passive"))
      (node (ref "R51") (pin "1") (pinfunction "1_1") (pintype "passive"))
      (node (ref "R52") (pin "2") (pinfunction "2_2") (pintype "passive"))
    )
    (net (code "42") (name "Net-(Q7-PadE)") (class "Default")
      (node (ref "Q7") (pin "E") (pinfunction "E_E") (pintype "passive"))
      (node (ref "Q9") (pin "B") (pinfunction "B_B") (pintype "passive"))
      (node (ref "R50") (pin "1") (pinfunction "1_1") (pintype "passive"))
      (node (ref "R54") (pin "2") (pinfunction "2_2") (pintype "passive"))
    )
    (net (code "43") (name "Net-(Q8-PadB)") (class "Default")
      (node (ref "Q8") (pin "B") (pinfunction "B_B") (pintype "passive"))
      (node (ref "R48") (pin "1") (pinfunction "1_1") (pintype "passive"))
      (node (ref "R53") (pin "1") (pinfunction "1_1") (pintype "passive"))
    )
    (net (code "44") (name "Net-(Q10-PadB)") (class "Default")
      (node (ref "Q10") (pin "B") (pinfunction "B_B") (pintype "passive"))
      (node (ref "Q8") (pin "E") (pinfunction "E_E") (pintype "passive"))
      (node (ref "R53") (pin "2") (pinfunction "2_2") (pintype "passive"))
      (node (ref "R55") (pin "2") (pinfunction "2_2") (pintype "passive"))
    )
    (net (code "45") (name "Net-(Q13-PadC)") (class "Default")
      (node (ref "Q13") (pin "C") (pinfunction "C_C") (pintype "passive"))
      (node (ref "R63") (pin "2") (pinfunction "2_2") (pintype "passive"))
    )
    (net (code "46") (name "Net-(Q14-PadB)") (class "Default")
      (node (ref "Q14") (pin "B") (pinfunction "B_B") (pintype "passive"))
      (node (ref "R61") (pin "2") (pinfunction "2_2") (pintype "passive"))
      (node (ref "R62") (pin "2") (pinfunction "2_2") (pintype "passive"))
      (node (ref "R63") (pin "1") (pinfunction "1_1") (pintype "passive"))
    )
    (net (code "47") (name "Net-(Q14-PadE)") (class "Default")
      (node (ref "Q14") (pin "E") (pinfunction "E_E") (pintype "passive"))
      (node (ref "Q16") (pin "B") (pinfunction "B_B") (pintype "passive"))
      (node (ref "R62") (pin "1") (pinfunction "1_1") (pintype "passive"))
      (node (ref "R67") (pin "2") (pinfunction "2_2") (pintype "passive"))
    )
    (net (code "48") (name "Net-(Q15-PadB)") (class "Default")
      (node (ref "Q15") (pin "B") (pinfunction "B_B") (pintype "passive"))
      (node (ref "R59") (pin "1") (pinfunction "1_1") (pintype "passive"))
      (node (ref "R64") (pin "1") (pinfunction "1_1") (pintype "passive"))
    )
    (net (code "49") (name "Net-(Q15-PadE)") (class "Default")
      (node (ref "Q15") (pin "E") (pinfunction "E_E") (pintype "passive"))
      (node (ref "Q17") (pin "B") (pinfunction "B_B") (pintype "passive"))
      (node (ref "R64") (pin "2") (pinfunction "2_2") (pintype "passive"))
      (node (ref "R68") (pin "2") (pinfunction "2_2") (pintype "passive"))
    )
    (net (code "50") (name "Net-(R41-Pad1)") (class "Default")
      (node (ref "R41") (pin "1") (pinfunction "1_1") (pintype "passive"))
      (node (ref "R42") (pin "2") (pinfunction "2_2") (pintype "passive"))
    )
    (net (code "51") (name "Net-(R45-Pad1)") (class "Default")
      (node (ref "R45") (pin "1") (pinfunction "1_1") (pintype "passive"))
      (node (ref "R46") (pin "2") (pinfunction "2_2") (pintype "passive"))
    )
    (net (code "52") (name "Net-(U4-EN)") (class "Default")
      (node (ref "C29") (pin "1") (pinfunction "1_1") (pintype "passive"))
      (node (ref "L2") (pin "1") (pinfunction "1_1") (pintype "passive"))
      (node (ref "R75") (pin "2") (pinfunction "2_2") (pintype "passive"))
      (node (ref "U4") (pin "4") (pinfunction "EN_4") (pintype "passive"))
      (node (ref "U4") (pin "5") (pinfunction "IN_5") (pintype "passive"))
    )
    (net (code "53") (name "Net-(U4-FB)") (class "Default")
      (node (ref "C31") (pin "2") (pinfunction "2_2") (pintype "passive"))
      (node (ref "R22") (pin "2") (pinfunction "2_2") (pintype "passive"))
      (node (ref "R23") (pin "2") (pinfunction "2_2") (pintype "passive"))
      (node (ref "U4") (pin "3") (pinfunction "FB_3") (pintype "passive"))
    )
    (net (code "54") (name "Net-(U4-SW)") (class "Default")
      (node (ref "D3") (pin "1") (pinfunction "1_1") (pintype "passive"))
      (node (ref "L2") (pin "2") (pinfunction "2_2") (pintype "passive"))
      (node (ref "U4") (pin "1") (pinfunction "SW_1") (pintype "passive"))
    )
    (net (code "55") (name "Net-(U5-PROG)") (class "Default")
      (node (ref "R21") (pin "1") (pinfunction "1_1") (pintype "passive"))
      (node (ref "U5") (pin "2") (pinfunction "PROG_2") (pintype "passive"))
    )
    (net (code "56") (name "Net-(U6-FB)") (class "Default")
      (node (ref "R35") (pin "1") (pinfunction "1_1") (pintype "passive"))
      (node (ref "R36") (pin "1") (pinfunction "1_1") (pintype "passive"))
      (node (ref "U6") (pin "4") (pinfunction "FB_4") (pintype "passive"))
    )
    (net (code "57") (name "Net-(U6-SW1)") (class "Default")
      (node (ref "L3") (pin "1") (pinfunction "1_1") (pintype "passive"))
      (node (ref "U6") (pin "9") (pinfunction "SW1_9") (pintype "passive"))
    )
    (net (code "58") (name "Net-(U6-SW2)") (class "Default")
      (node (ref "L3") (pin "2") (pinfunction "2_2") (pintype "passive"))
      (node (ref "U6") (pin "7") (pinfunction "SW2_7") (pintype "passive"))
    )
    (net (code "59") (name "Net-(U7-COMP)") (class "Default")
      (node (ref "C42") (pin "2") (pinfunction "2_2") (pintype "passive"))
      (node (ref "R37") (pin "2") (pinfunction "2_2") (pintype "passive"))
      (node (ref "U7") (pin "3") (pinfunction "COMP_3") (pintype "passive"))
    )
    (net (code "60") (name "Net-(U7-CS)") (class "Default")
      (node (ref "Q5") (pin "S") (pinfunction "S_S") (pintype "passive"))
      (node (ref "R40") (pin "2") (pinfunction "2_2") (pintype "passive"))
      (node (ref "U7") (pin "6") (pinfunction "CS_6") (pintype "passive"))
    )
    (net (code "61") (name "Net-(U7-EXT)") (class "Default")
      (node (ref "Q5") (pin "G") (pinfunction "G_G") (pintype "passive"))
      (node (ref "U7") (pin "8") (pinfunction "EXT_8") (pintype "passive"))
    )
    (net (code "62") (name "Net-(U7-RT)") (class "Default")
      (node (ref "R32") (pin "2") (pinfunction "2_2") (pintype "passive"))
      (node (ref "U7") (pin "5") (pinfunction "RT_5") (pintype "passive"))
    )
    (net (code "63") (name "Net-(U7-VDS)") (class "Default")
      (node (ref "C38") (pin "2") (pinfunction "2_2") (pintype "passive"))
      (node (ref "U7") (pin "1") (pinfunction "VDS_1") (pintype "passive"))
    )
    (net (code "64") (name "Net-(U8-A)") (class "Default")
      (node (ref "R31") (pin "1") (pinfunction "1_1") (pintype "passive"))
      (node (ref "R34") (pin "1") (pinfunction "1_1") (pintype "passive"))
      (node (ref "U8") (pin "2") (pinfunction "A_2") (pintype "passive"))
    )
    (net (code "65") (name "Net-(U8-VCC)") (class "Default")
      (node (ref "C39") (pin "2") (pinfunction "2_2") (pintype "passive"))
      (node (ref "R33") (pin "2") (pinfunction "2_2") (pintype "passive"))
      (node (ref "U8") (pin "5") (pinfunction "VCC_5") (pintype "passive"))
      (node (ref "U9") (pin "1") (pinfunction "1_1") (pintype "passive"))
      (node (ref "U9") (pin "2") (pinfunction "2_2") (pintype "passive"))
    )
    (net (code "66") (name "Net-(U8-Y)") (class "Default")
      (node (ref "R38") (pin "2") (pinfunction "2_2") (pintype "passive"))
      (node (ref "U8") (pin "4") (pinfunction "Y_4") (pintype "passive"))
    )
    (net (code "67") (name "Net-(U10-RXD)") (class "Default")
      (node (ref "R73") (pin "2") (pinfunction "2_2") (pintype "passive"))
      (node (ref "U10") (pin "5") (pinfunction "RXD_5") (pintype "passive"))
    )
    (net (code "68") (name "Net-(U10-TXD)") (class "Default")
      (node (ref "D10") (pin "2") (pinfunction "2_2") (pintype "passive"))
      (node (ref "U10") (pin "4") (pinfunction "TXD_4") (pintype "passive"))
    )
    (net (code "69") (name "SOC_4.1V") (class "Default")
      (node (ref "C41") (pin "1") (pinfunction "1_1") (pintype "passive"))
      (node (ref "C43") (pin "1") (pinfunction "1_1") (pintype "passive"))
      (node (ref "R35") (pin "2") (pinfunction "2_2") (pintype "passive"))
      (node (ref "U6") (pin "6") (pinfunction "VOUT_6") (pintype "passive"))
    )
    (net (code "70") (name "SOC_VSYS") (class "Default")
      (node (ref "R74") (pin "1") (pinfunction "1_1") (pintype "passive"))
    )
    (net (code "71") (name "SYS_VBAT") (class "Default")
      (node (ref "C28") (pin "1") (pinfunction "1_1") (pintype "passive"))
      (node (ref "C32") (pin "1") (pinfunction "1_1") (pintype "passive"))
      (node (ref "J2") (pin "1") (pinfunction "1_1") (pintype "passive"))
      (node (ref "Q2") (pin "S") (pinfunction "S_S") (pintype "passive"))
      (node (ref "R20") (pin "2") (pinfunction "2_2") (pintype "passive"))
      (node (ref "U5") (pin "5") (pinfunction "BAT_5") (pintype "passive"))
    )
    (net (code "72") (name "SYS_VBUS") (class "Default")
      (node (ref "C34") (pin "1") (pinfunction "1_1") (pintype "passive"))
      (node (ref "C35") (pin "1") (pinfunction "1_1") (pintype "passive"))
      (node (ref "L4") (pin "1") (pinfunction "1_1") (pintype "passive"))
      (node (ref "Q2") (pin "D") (pinfunction "D_D") (pintype "passive"))
      (node (ref "R27") (pin "2") (pinfunction "2_2") (pintype "passive"))
      (node (ref "R75") (pin "1") (pinfunction "1_1") (pintype "passive"))
      (node (ref "U6") (pin "10") (pinfunction "VIN_10") (pintype "passive"))
    )
    (net (code "73") (name "VCC_HV") (class "Default")
      (node (ref "C46") (pin "1") (pinfunction "1_1") (pintype "passive"))
      (node (ref "C47") (pin "2") (pinfunction "2_2") (pintype "passive"))
      (node (ref "D4") (pin "2") (pinfunction "2_2") (pintype "passive"))
      (node (ref "D5") (pin "2") (pinfunction "2_2") (pintype "passive"))
      (node (ref "D6") (pin "2") (pinfunction "2_2") (pintype "passive"))
      (node (ref "Q16") (pin "E") (pinfunction "E_E") (pintype "passive"))
      (node (ref "Q9") (pin "E") (pinfunction "E_E") (pintype "passive"))
      (node (ref "R41") (pin "2") (pinfunction "2_2") (pintype "passive"))
      (node (ref "R44") (pin "2") (pinfunction "2_2") (pintype "passive"))
      (node (ref "R45") (pin "2") (pinfunction "2_2") (pintype "passive"))
      (node (ref "R52") (pin "1") (pinfunction "1_1") (pintype "passive"))
      (node (ref "R54") (pin "1") (pinfunction "1_1") (pintype "passive"))
      (node (ref "R61") (pin "1") (pinfunction "1_1") (pintype "passive"))
      (node (ref "R67") (pin "1") (pinfunction "1_1") (pintype "passive"))
    )
    (net (code "74") (name "VIN_USB") (class "Default")
      (node (ref "C30") (pin "1") (pinfunction "1_1") (pintype "passive"))
      (node (ref "C54") (pin "1") (pinfunction "1_1") (pintype "passive"))
      (node (ref "J3") (pin "A4/B9") (pinfunction "VBUS_A4/B9") (pintype "passive"))
      (node (ref "J3") (pin "B4/A9") (pinfunction "VBUS_B4/A9") (pintype "passive"))
      (node (ref "R18") (pin "2") (pinfunction "2_2") (pintype "passive"))
      (node (ref "R28") (pin "2") (pinfunction "2_2") (pintype "passive"))
      (node (ref "U10") (pin "3") (pinfunction "VDD5_3") (pintype "passive"))
      (node (ref "U10") (pin "9") (pinfunction "VBUS_9") (pintype "passive"))
      (node (ref "U5") (pin "4") (pinfunction "VCC_4") (pintype "passive"))
    )
    (net (code "75") (name "WCH_3V3") (class "Default")
      (node (ref "C55") (pin "2") (pinfunction "2_2") (pintype "passive"))
      (node (ref "U10") (pin "1") (pinfunction "VIO_1") (pintype "passive"))
      (node (ref "U10") (pin "6") (pinfunction "V3_6") (pintype "passive"))
    )
    (net (code "76") (name "unconnected-(J3-SBU1-PadA8)") (class "Default")
      (node (ref "J3") (pin "A8") (pinfunction "SBU1_A8") (pintype "passive"))
    )
    (net (code "77") (name "unconnected-(J3-SBU2-PadB8)") (class "Default")
      (node (ref "J3") (pin "B8") (pinfunction "SBU2_B8") (pintype "passive"))
    )
    (net (code "78") (name "unconnected-(U4-NC-Pad6)") (class "Default")
      (node (ref "U4") (pin "6") (pinfunction "NC_6") (pintype "passive"))
    )
    (net (code "79") (name "unconnected-(U5-~{STDBY}-Pad6)") (class "Default")
      (node (ref "U5") (pin "6") (pinfunction "~{STDBY}_6") (pintype "passive"))
    )
    (net (code "80") (name "unconnected-(U6-PG-Pad5)") (class "Default")
      (node (ref "U6") (pin "5") (pinfunction "PG_5") (pintype "passive"))
    )
    (net (code "81") (name "unconnected-(U10-ACT#-Pad10)") (class "Default")
      (node (ref "U10") (pin "10") (pinfunction "ACT#_10") (pintype "passive"))
    )
    (net (code "82") (name "unconnected-(U10-CTS-Pad15)") (class "Default")
      (node (ref "U10") (pin "15") (pinfunction "CTS_15") (pintype "passive"))
    )
    (net (code "83") (name "unconnected-(U10-DCD-Pad11)") (class "Default")
      (node (ref "U10") (pin "11") (pinfunction "DCD_11") (pintype "passive"))
    )
    (net (code "84") (name "unconnected-(U10-DSR-Pad14)") (class "Default")
      (node (ref "U10") (pin "14") (pinfunction "DSR_14") (pintype "passive"))
    )
    (net (code "85") (name "unconnected-(U10-DTR-Pad12)") (class "Default")
      (node (ref "U10") (pin "12") (pinfunction "DTR_12") (pintype "passive"))
    )
    (net (code "86") (name "unconnected-(U10-RI-Pad16)") (class "Default")
      (node (ref "U10") (pin "16") (pinfunction "RI_16") (pintype "passive"))
    )
    (net (code "87") (name "unconnected-(U10-RTS-Pad13)") (class "Default")
      (node (ref "U10") (pin "13") (pinfunction "RTS_13") (pintype "passive"))
    )
  )
)
